# Keg_Cop_-_Sensors.net
KiCad netlist of a schematic drawn in EAGLE
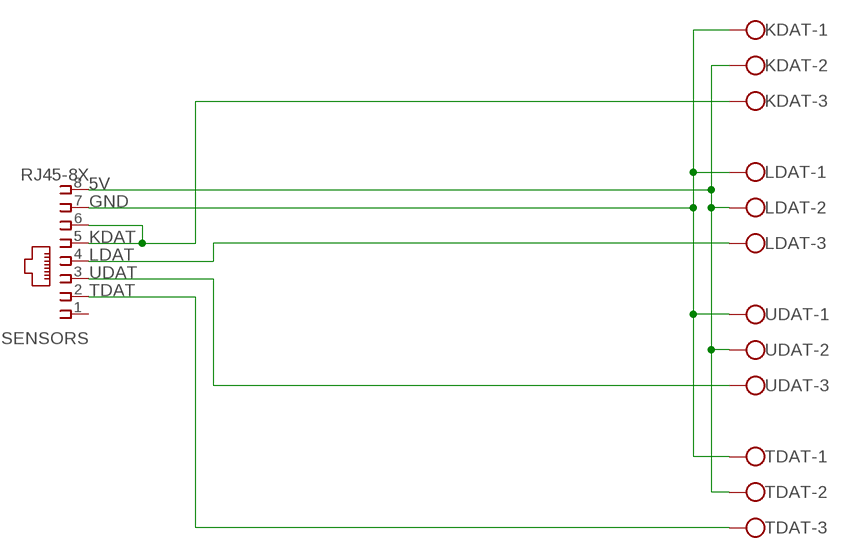
[diagram p0: schematic, sheet 1]

(export (version "E")
  (design (tool "Eeschema 10.0.6"))
  (components
    (comp (ref "KDAT")
      (value "W237-103")
      (footprint "eagle-import:W237-103")
      (fields (field (name "MPN") "237-103"))
      (libsource (lib "eagle-import") (part "W237-103"))
    )
    (comp (ref "LDAT")
      (value "W237-103")
      (footprint "eagle-import:W237-103")
      (fields (field (name "MPN") "237-103"))
      (libsource (lib "eagle-import") (part "W237-103"))
    )
    (comp (ref "SENSORS")
      (value "RJ45-8X")
      (footprint "eagle-import:RJ45-NO-SHIELD")
      (libsource (lib "eagle-import") (part "RJ45-8X"))
    )
    (comp (ref "TDAT")
      (value "W237-103")
      (footprint "eagle-import:W237-103")
      (fields (field (name "MPN") "237-103"))
      (libsource (lib "eagle-import") (part "W237-103"))
    )
    (comp (ref "UDAT")
      (value "W237-103")
      (footprint "eagle-import:W237-103")
      (fields (field (name "MPN") "237-103"))
      (libsource (lib "eagle-import") (part "W237-103"))
    )
  )
  (nets
    (net (code "1") (name "/5V") (class "Default")
      (node (ref "KDAT") (pin "2") (pinfunction "KL_2") (pintype "passive"))
      (node (ref "LDAT") (pin "2") (pinfunction "KL_2") (pintype "passive"))
      (node (ref "SENSORS") (pin "8") (pinfunction "8_8") (pintype "passive"))
      (node (ref "TDAT") (pin "2") (pinfunction "KL_2") (pintype "passive"))
      (node (ref "UDAT") (pin "2") (pinfunction "KL_2") (pintype "passive"))
    )
    (net (code "2") (name "/GND") (class "Default")
      (node (ref "KDAT") (pin "1") (pinfunction "KL_1") (pintype "passive"))
      (node (ref "LDAT") (pin "1") (pinfunction "KL_1") (pintype "passive"))
      (node (ref "SENSORS") (pin "7") (pinfunction "7_7") (pintype "passive"))
      (node (ref "TDAT") (pin "1") (pinfunction "KL_1") (pintype "passive"))
      (node (ref "UDAT") (pin "1") (pinfunction "KL_1") (pintype "passive"))
    )
    (net (code "3") (name "/KDAT") (class "Default")
      (node (ref "KDAT") (pin "3") (pinfunction "KL_3") (pintype "passive"))
      (node (ref "SENSORS") (pin "5") (pinfunction "5_5") (pintype "passive"))
      (node (ref "SENSORS") (pin "6") (pinfunction "6_6") (pintype "passive"))
    )
    (net (code "4") (name "/LDAT") (class "Default")
      (node (ref "LDAT") (pin "3") (pinfunction "KL_3") (pintype "passive"))
      (node (ref "SENSORS") (pin "4") (pinfunction "4_4") (pintype "passive"))
    )
    (net (code "5") (name "/TDAT") (class "Default")
      (node (ref "SENSORS") (pin "2") (pinfunction "2_2") (pintype "passive"))
      (node (ref "TDAT") (pin "3") (pinfunction "KL_3") (pintype "passive"))
    )
    (net (code "6") (name "/UDAT") (class "Default")
      (node (ref "SENSORS") (pin "3") (pinfunction "3_3") (pintype "passive"))
      (node (ref "UDAT") (pin "3") (pinfunction "KL_3") (pintype "passive"))
    )
    (net (code "7") (name "unconnected-(SENSORS-Pad1)") (class "Default")
      (node (ref "SENSORS") (pin "1") (pinfunction "1_1") (pintype "passive"))
    )
  )
)
